# FRAM.net
KiCad netlist of a schematic drawn in Altium Designer
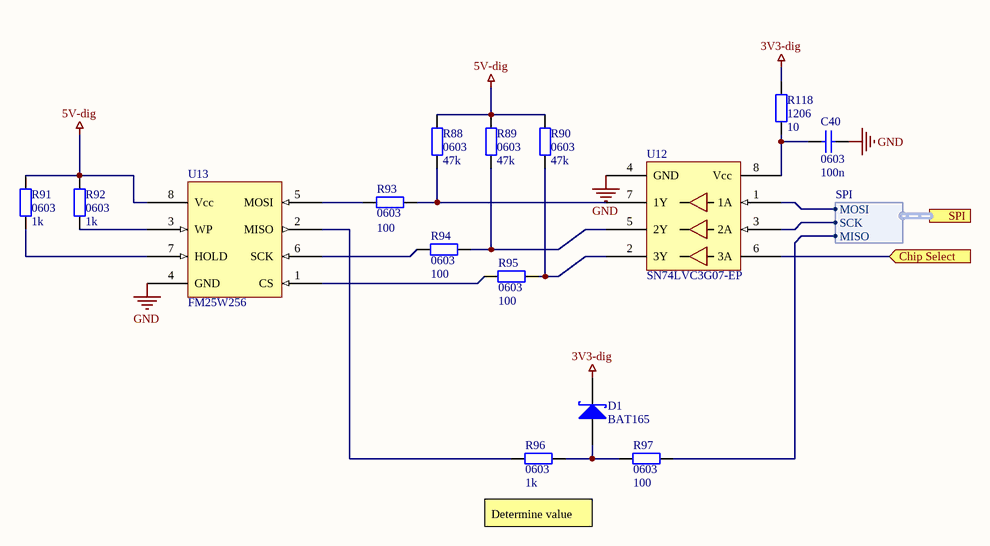
[diagram p0: FRAM.SchDoc]

(export (version "E")
  (design (tool "Eeschema 10.0.6"))
  (components
    (comp (ref "C40")
      (value "0603")
      (footprint "SMD_Capacitor_0603")
      (description "Capacitor")
      (fields (field (name "ALTIUM_VALUE") "100n") (field (name "PUBLISHER") "Altium Limited"))
      (libsource (lib "Miscellaneous Devices") (part "Cap"))
    )
    (comp (ref "D1")
      (value "BAT165")
      (footprint "SOD323")
      (description "Madium Power AF Schottky 750mA 40V Diode")
      (fields (field (name "MANUFACTURER") "Infineon"))
      (libsource (lib "diodes_switching") (part "BAT165"))
    )
    (comp (ref "R88")
      (value "0603")
      (footprint "SMD_Resistor_0603")
      (description "Resistor")
      (fields (field (name "ALTIUM_VALUE") "47k") (field (name "PUBLISHER") "Altium Limited"))
      (libsource (lib "") (part "Res2_3"))
    )
    (comp (ref "R89")
      (value "0603")
      (footprint "SMD_Resistor_0603")
      (description "Resistor")
      (fields (field (name "ALTIUM_VALUE") "47k") (field (name "PUBLISHER") "Altium Limited"))
      (libsource (lib "") (part "Res2_3"))
    )
    (comp (ref "R90")
      (value "0603")
      (footprint "SMD_Resistor_0603")
      (description "Resistor")
      (fields (field (name "ALTIUM_VALUE") "47k") (field (name "PUBLISHER") "Altium Limited"))
      (libsource (lib "") (part "Res2_3"))
    )
    (comp (ref "R91")
      (value "0603")
      (footprint "SMD_Resistor_0603")
      (description "Resistor")
      (fields (field (name "ALTIUM_VALUE") "1k") (field (name "PUBLISHER") "Altium Limited"))
      (libsource (lib "") (part "Res2_1"))
    )
    (comp (ref "R92")
      (value "0603")
      (footprint "SMD_Resistor_0603")
      (description "Resistor")
      (fields (field (name "ALTIUM_VALUE") "1k") (field (name "PUBLISHER") "Altium Limited"))
      (libsource (lib "") (part "Res2_1"))
    )
    (comp (ref "R93")
      (value "0603")
      (footprint "SMD_Resistor_0603")
      (description "Resistor")
      (fields (field (name "ALTIUM_VALUE") "100") (field (name "PUBLISHER") "Altium Limited"))
      (libsource (lib "Miscellaneous Devices") (part "Res2"))
    )
    (comp (ref "R94")
      (value "0603")
      (footprint "SMD_Resistor_0603")
      (description "Resistor")
      (fields (field (name "ALTIUM_VALUE") "100") (field (name "PUBLISHER") "Altium Limited"))
      (libsource (lib "Miscellaneous Devices") (part "Res2"))
    )
    (comp (ref "R95")
      (value "0603")
      (footprint "SMD_Resistor_0603")
      (description "Resistor")
      (fields (field (name "ALTIUM_VALUE") "100") (field (name "PUBLISHER") "Altium Limited"))
      (libsource (lib "Miscellaneous Devices") (part "Res2"))
    )
    (comp (ref "R96")
      (value "0603")
      (footprint "SMD_Resistor_0603")
      (description "Resistor")
      (fields (field (name "ALTIUM_VALUE") "1k") (field (name "PUBLISHER") "Altium Limited"))
      (libsource (lib "Miscellaneous Devices") (part "Res2"))
    )
    (comp (ref "R97")
      (value "0603")
      (footprint "SMD_Resistor_0603")
      (description "Resistor")
      (fields (field (name "ALTIUM_VALUE") "100") (field (name "PUBLISHER") "Altium Limited"))
      (libsource (lib "Miscellaneous Devices") (part "Res2"))
    )
    (comp (ref "R118")
      (value "1206")
      (footprint "SMD_Resistor_1206")
      (description "Resistor")
      (fields (field (name "ALTIUM_VALUE") "10") (field (name "PUBLISHER") "Altium Limited"))
      (libsource (lib "") (part "Res2_2"))
    )
    (comp (ref "U12")
      (value "SN74LVC3G07-EP")
      (footprint "VSSOP-8")
      (description "Triple Buffer/Driver With Open-Drain Output")
      (libsource (lib "microcircuits_miscellaneous") (part "SN74LVC3G07-EP"))
    )
    (comp (ref "U13")
      (value "FM25W256")
      (footprint "SOIC-8-N")
      (description "256Kb (8k x 32) SPI F-RAM")
      (libsource (lib "microcircuits_miscellaneous") (part "FM25W256"))
    )
  )
  (nets
    (net (code "2") (name "/Chip Select") (class "Default")
      (node (ref "U12") (pin "6") (pinfunction "3A_6") (pintype "passive"))
    )
    (net (code "3") (name "/MISO") (class "Default")
      (node (ref "R97") (pin "1") (pinfunction "1_1") (pintype "passive"))
    )
    (net (code "4") (name "/MOSI") (class "Default")
      (node (ref "U12") (pin "1") (pinfunction "1A_1") (pintype "input"))
    )
    (net (code "5") (name "/SCK") (class "Default")
      (node (ref "U12") (pin "3") (pinfunction "2A_3") (pintype "input"))
    )
    (net (code "7") (name "3V3-dig") (class "Default")
      (node (ref "D1") (pin "K") (pinfunction "K_K") (pintype "passive"))
      (node (ref "R118") (pin "1") (pinfunction "1_1") (pintype "passive"))
    )
    (net (code "8") (name "5V-dig") (class "Default")
      (node (ref "R88") (pin "2") (pinfunction "2_2") (pintype "passive"))
      (node (ref "R89") (pin "2") (pinfunction "2_2") (pintype "passive"))
      (node (ref "R90") (pin "2") (pinfunction "2_2") (pintype "passive"))
      (node (ref "R91") (pin "2") (pinfunction "2_2") (pintype "passive"))
      (node (ref "R92") (pin "2") (pinfunction "2_2") (pintype "passive"))
      (node (ref "U13") (pin "8") (pinfunction "Vcc_8") (pintype "power_in"))
    )
    (net (code "9") (name "GND") (class "Default")
      (node (ref "C40") (pin "1") (pinfunction "1_1") (pintype "passive"))
      (node (ref "U12") (pin "4") (pinfunction "GND_4") (pintype "power_in"))
      (node (ref "U13") (pin "4") (pinfunction "GND_4") (pintype "power_in"))
    )
    (net (code "10") (name "Net-(D1-PadA)") (class "Default")
      (node (ref "D1") (pin "A") (pinfunction "A_A") (pintype "passive"))
      (node (ref "R96") (pin "1") (pinfunction "1_1") (pintype "passive"))
      (node (ref "R97") (pin "2") (pinfunction "2_2") (pintype "passive"))
    )
    (net (code "11") (name "Net-(U12-1Y)") (class "Default")
      (node (ref "R88") (pin "1") (pinfunction "1_1") (pintype "passive"))
      (node (ref "R93") (pin "1") (pinfunction "1_1") (pintype "passive"))
      (node (ref "U12") (pin "7") (pinfunction "1Y_7") (pintype "open_collector"))
    )
    (net (code "12") (name "Net-(U12-2Y)") (class "Default")
      (node (ref "R89") (pin "1") (pinfunction "1_1") (pintype "passive"))
      (node (ref "R94") (pin "1") (pinfunction "1_1") (pintype "passive"))
      (node (ref "U12") (pin "5") (pinfunction "2Y_5") (pintype "open_collector"))
    )
    (net (code "13") (name "Net-(U12-3Y)") (class "Default")
      (node (ref "R90") (pin "1") (pinfunction "1_1") (pintype "passive"))
      (node (ref "R95") (pin "1") (pinfunction "1_1") (pintype "passive"))
      (node (ref "U12") (pin "2") (pinfunction "3Y_2") (pintype "open_collector"))
    )
    (net (code "14") (name "Net-(U12-Vcc)") (class "Default")
      (node (ref "C40") (pin "2") (pinfunction "2_2") (pintype "passive"))
      (node (ref "R118") (pin "2") (pinfunction "2_2") (pintype "passive"))
      (node (ref "U12") (pin "8") (pinfunction "Vcc_8") (pintype "power_in"))
    )
    (net (code "15") (name "Net-(U13-CS)") (class "Default")
      (node (ref "R95") (pin "2") (pinfunction "2_2") (pintype "passive"))
      (node (ref "U13") (pin "1") (pinfunction "CS_1") (pintype "input"))
    )
    (net (code "16") (name "Net-(U13-HOLD)") (class "Default")
      (node (ref "R91") (pin "1") (pinfunction "1_1") (pintype "passive"))
      (node (ref "U13") (pin "7") (pinfunction "HOLD_7") (pintype "input"))
    )
    (net (code "17") (name "Net-(U13-MISO)") (class "Default")
      (node (ref "R96") (pin "2") (pinfunction "2_2") (pintype "passive"))
      (node (ref "U13") (pin "2") (pinfunction "MISO_2") (pintype "output"))
    )
    (net (code "18") (name "Net-(U13-MOSI)") (class "Default")
      (node (ref "R93") (pin "2") (pinfunction "2_2") (pintype "passive"))
      (node (ref "U13") (pin "5") (pinfunction "MOSI_5") (pintype "input"))
    )
    (net (code "19") (name "Net-(U13-SCK)") (class "Default")
      (node (ref "R94") (pin "2") (pinfunction "2_2") (pintype "passive"))
      (node (ref "U13") (pin "6") (pinfunction "SCK_6") (pintype "input"))
    )
    (net (code "20") (name "Net-(U13-WP)") (class "Default")
      (node (ref "R92") (pin "1") (pinfunction "1_1") (pintype "passive"))
      (node (ref "U13") (pin "3") (pinfunction "WP_3") (pintype "input"))
    )
  )
)
